# VAM_control_logic_proposal_4_5.net
KiCad netlist of a schematic drawn in EAGLE
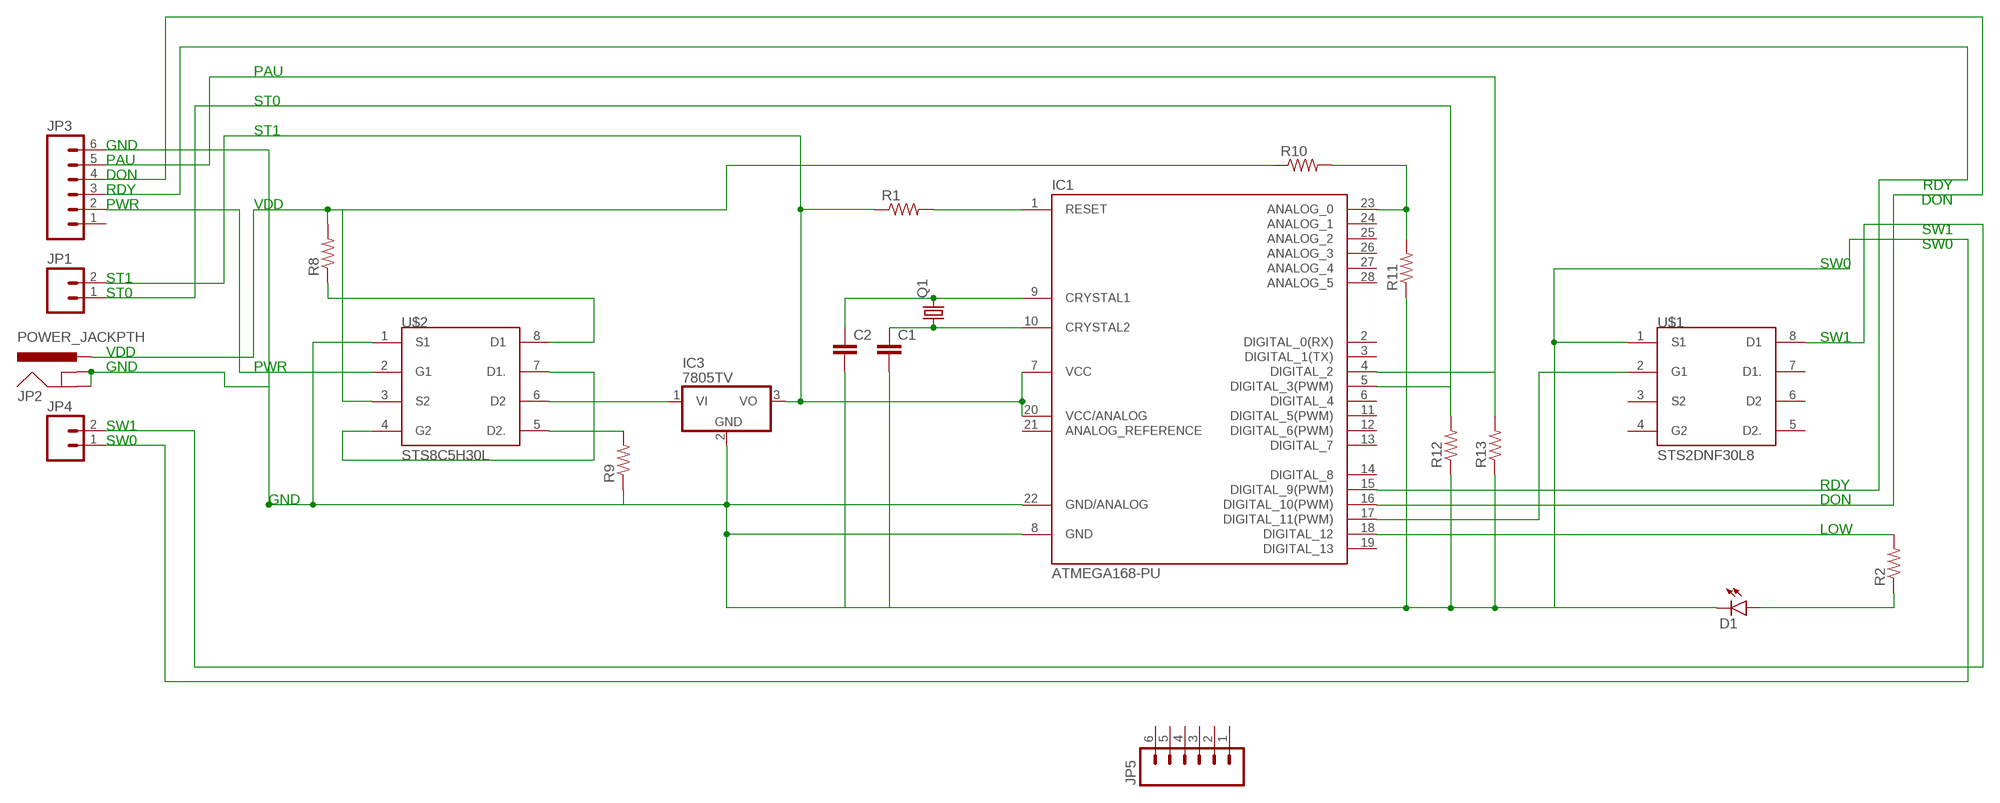
[diagram p0: schematic, sheet 1]

(export (version "E")
  (design (tool "Eeschema 10.0.6"))
  (components
    (comp (ref "C1")
      (value "C-EU025-024X044")
      (footprint "eagle-import:C025-024X044")
      (libsource (lib "eagle-import") (part "C-EU025-024X044"))
    )
    (comp (ref "C2")
      (value "C-EU025-024X044")
      (footprint "eagle-import:C025-024X044")
      (libsource (lib "eagle-import") (part "C-EU025-024X044"))
    )
    (comp (ref "D1")
      (value "LED5MM")
      (footprint "eagle-import:LED5MM")
      (libsource (lib "eagle-import") (part "LED5MM"))
    )
    (comp (ref "IC1")
      (value "ATMEGA168-PU")
      (footprint "eagle-import:DIL28-3")
      (libsource (lib "eagle-import") (part "ATMEGA168-PU"))
    )
    (comp (ref "IC3")
      (value "7805TV")
      (footprint "eagle-import:TO220V")
      (libsource (lib "eagle-import") (part "78TV05"))
    )
    (comp (ref "JP1")
      (value "M02PTH")
      (footprint "eagle-import:1X02")
      (libsource (lib "eagle-import") (part "M02PTH"))
    )
    (comp (ref "JP2")
      (value "POWER_JACKPTH")
      (footprint "eagle-import:POWER_JACK_PTH")
      (libsource (lib "eagle-import") (part "POWER_JACKPTH"))
    )
    (comp (ref "JP3")
      (value "M06SILK_FEMALE_PTH")
      (footprint "eagle-import:1X06")
      (libsource (lib "eagle-import") (part "M06SILK_FEMALE_PTH"))
    )
    (comp (ref "JP4")
      (value "M02PTH")
      (footprint "eagle-import:1X02")
      (libsource (lib "eagle-import") (part "M02PTH"))
    )
    (comp (ref "JP5")
      (value "M06SILK_FEMALE_PTH")
      (footprint "eagle-import:1X06")
      (libsource (lib "eagle-import") (part "M06SILK_FEMALE_PTH"))
    )
    (comp (ref "Q1")
      (value "CRYSTALHC49U-V")
      (footprint "eagle-import:HC49U-V")
      (libsource (lib "eagle-import") (part "CRYSTALHC49U-V"))
    )
    (comp (ref "R1")
      (value "R-US_R1206")
      (footprint "eagle-import:R1206")
      (libsource (lib "eagle-import") (part "R-US_R1206"))
    )
    (comp (ref "R2")
      (value "R-US_R1206")
      (footprint "eagle-import:R1206")
      (libsource (lib "eagle-import") (part "R-US_R1206"))
    )
    (comp (ref "R8")
      (value "R-US_R1206")
      (footprint "eagle-import:R1206")
      (libsource (lib "eagle-import") (part "R-US_R1206"))
    )
    (comp (ref "R9")
      (value "R-US_R1206")
      (footprint "eagle-import:R1206")
      (libsource (lib "eagle-import") (part "R-US_R1206"))
    )
    (comp (ref "R10")
      (value "R-US_R1206")
      (footprint "eagle-import:R1206")
      (libsource (lib "eagle-import") (part "R-US_R1206"))
    )
    (comp (ref "R11")
      (value "R-US_R1206")
      (footprint "eagle-import:R1206")
      (libsource (lib "eagle-import") (part "R-US_R1206"))
    )
    (comp (ref "R12")
      (value "R-US_R1206")
      (footprint "eagle-import:R1206")
      (libsource (lib "eagle-import") (part "R-US_R1206"))
    )
    (comp (ref "R13")
      (value "R-US_R1206")
      (footprint "eagle-import:R1206")
      (libsource (lib "eagle-import") (part "R-US_R1206"))
    )
    (comp (ref "U$1")
      (value "STS2DNF30L8")
      (footprint "eagle-import:SOIC-8")
      (libsource (lib "eagle-import") (part "STS2DNF30L8"))
    )
    (comp (ref "U$2")
      (value "STS8C5H30L")
      (footprint "eagle-import:SOIC-8")
      (libsource (lib "eagle-import") (part "STS2DNF30L8"))
    )
  )
  (nets
    (net (code "1") (name "Net-(D1-C)") (class "Default")
      (node (ref "C1") (pin "2") (pinfunction "2_2") (pintype "passive"))
      (node (ref "C2") (pin "2") (pinfunction "2_2") (pintype "passive"))
      (node (ref "D1") (pin "K") (pinfunction "C_K") (pintype "passive"))
      (node (ref "IC1") (pin "22") (pinfunction "GND/ANALOG_22") (pintype "power_in"))
      (node (ref "IC1") (pin "8") (pinfunction "GND_8") (pintype "power_in"))
      (node (ref "IC3") (pin "2") (pinfunction "GND_2") (pintype "passive"))
      (node (ref "JP2") (pin "GND") (pinfunction "GND_GND") (pintype "bidirectional"))
      (node (ref "JP2") (pin "GNDBREAK") (pinfunction "GNDBREAK_GNDBREAK") (pintype "bidirectional"))
      (node (ref "JP3") (pin "6") (pinfunction "6_6") (pintype "passive"))
      (node (ref "JP4") (pin "1") (pinfunction "1_1") (pintype "passive"))
      (node (ref "R11") (pin "1") (pinfunction "1_1") (pintype "passive"))
      (node (ref "R12") (pin "1") (pinfunction "1_1") (pintype "passive"))
      (node (ref "R13") (pin "1") (pinfunction "1_1") (pintype "passive"))
      (node (ref "R9") (pin "1") (pinfunction "1_1") (pintype "passive"))
      (node (ref "U$1") (pin "1") (pinfunction "S1_1") (pintype "bidirectional"))
      (node (ref "U$2") (pin "1") (pinfunction "S1_1") (pintype "bidirectional"))
    )
    (net (code "2") (name "Net-(D1-PadA)") (class "Default")
      (node (ref "D1") (pin "A") (pinfunction "A_A") (pintype "passive"))
      (node (ref "R2") (pin "1") (pinfunction "1_1") (pintype "passive"))
    )
    (net (code "3") (name "Net-(IC1-ANALOG_0)") (class "Default")
      (node (ref "IC1") (pin "23") (pinfunction "ANALOG_0_23") (pintype "bidirectional"))
      (node (ref "R10") (pin "2") (pinfunction "2_2") (pintype "passive"))
      (node (ref "R11") (pin "2") (pinfunction "2_2") (pintype "passive"))
    )
    (net (code "4") (name "Net-(IC1-CRYSTAL1)") (class "Default")
      (node (ref "C2") (pin "1") (pinfunction "1_1") (pintype "passive"))
      (node (ref "IC1") (pin "9") (pinfunction "CRYSTAL1_9") (pintype "bidirectional"))
      (node (ref "Q1") (pin "2") (pinfunction "2_2") (pintype "passive"))
    )
    (net (code "5") (name "Net-(IC1-CRYSTAL2)") (class "Default")
      (node (ref "C1") (pin "1") (pinfunction "1_1") (pintype "passive"))
      (node (ref "IC1") (pin "10") (pinfunction "CRYSTAL2_10") (pintype "bidirectional"))
      (node (ref "Q1") (pin "1") (pinfunction "1_1") (pintype "passive"))
    )
    (net (code "6") (name "Net-(IC1-DIGITAL_2)") (class "Default")
      (node (ref "IC1") (pin "4") (pinfunction "DIGITAL_2_4") (pintype "bidirectional"))
      (node (ref "JP3") (pin "5") (pinfunction "5_5") (pintype "passive"))
      (node (ref "R13") (pin "2") (pinfunction "2_2") (pintype "passive"))
    )
    (net (code "7") (name "Net-(IC1-DIGITAL_3(PWM))") (class "Default")
      (node (ref "IC1") (pin "5") (pinfunction "DIGITAL_3(PWM)_5") (pintype "bidirectional"))
      (node (ref "JP1") (pin "1") (pinfunction "1_1") (pintype "passive"))
      (node (ref "R12") (pin "2") (pinfunction "2_2") (pintype "passive"))
    )
    (net (code "8") (name "Net-(IC1-DIGITAL_9(PWM))") (class "Default")
      (node (ref "IC1") (pin "15") (pinfunction "DIGITAL_9(PWM)_15") (pintype "bidirectional"))
      (node (ref "JP3") (pin "3") (pinfunction "3_3") (pintype "passive"))
    )
    (net (code "9") (name "Net-(IC1-DIGITAL_10(PWM))") (class "Default")
      (node (ref "IC1") (pin "16") (pinfunction "DIGITAL_10(PWM)_16") (pintype "bidirectional"))
      (node (ref "JP3") (pin "4") (pinfunction "4_4") (pintype "passive"))
    )
    (net (code "10") (name "Net-(IC1-DIGITAL_11(PWM))") (class "Default")
      (node (ref "IC1") (pin "17") (pinfunction "DIGITAL_11(PWM)_17") (pintype "bidirectional"))
      (node (ref "U$1") (pin "2") (pinfunction "G1_2") (pintype "bidirectional"))
    )
    (net (code "11") (name "Net-(IC1-DIGITAL_12)") (class "Default")
      (node (ref "IC1") (pin "18") (pinfunction "DIGITAL_12_18") (pintype "bidirectional"))
      (node (ref "R2") (pin "2") (pinfunction "2_2") (pintype "passive"))
    )
    (net (code "12") (name "Net-(IC1-RESET)") (class "Default")
      (node (ref "IC1") (pin "1") (pinfunction "RESET_1") (pintype "bidirectional"))
      (node (ref "R1") (pin "2") (pinfunction "2_2") (pintype "passive"))
    )
    (net (code "13") (name "Net-(IC1-VCC)") (class "Default")
      (node (ref "IC1") (pin "20") (pinfunction "VCC/ANALOG_20") (pintype "passive"))
      (node (ref "IC1") (pin "7") (pinfunction "VCC_7") (pintype "power_in"))
      (node (ref "IC3") (pin "3") (pinfunction "VO_3") (pintype "passive"))
      (node (ref "JP1") (pin "2") (pinfunction "2_2") (pintype "passive"))
      (node (ref "R1") (pin "1") (pinfunction "1_1") (pintype "passive"))
    )
    (net (code "14") (name "Net-(IC3-VI)") (class "Default")
      (node (ref "IC3") (pin "1") (pinfunction "VI_1") (pintype "input"))
      (node (ref "U$2") (pin "6") (pinfunction "D2_6") (pintype "bidirectional"))
    )
    (net (code "15") (name "Net-(U$1-D1)") (class "Default")
      (node (ref "JP4") (pin "2") (pinfunction "2_2") (pintype "passive"))
      (node (ref "U$1") (pin "8") (pinfunction "D1_8") (pintype "bidirectional"))
    )
    (net (code "16") (name "Net-(U$2-D1)") (class "Default")
      (node (ref "R8") (pin "1") (pinfunction "1_1") (pintype "passive"))
      (node (ref "U$2") (pin "8") (pinfunction "D1_8") (pintype "bidirectional"))
    )
    (net (code "17") (name "Net-(U$2-D1.)") (class "Default")
      (node (ref "U$2") (pin "4") (pinfunction "G2_4") (pintype "bidirectional"))
      (node (ref "U$2") (pin "7") (pinfunction "D1._7") (pintype "bidirectional"))
    )
    (net (code "18") (name "Net-(U$2-D2.)") (class "Default")
      (node (ref "R9") (pin "2") (pinfunction "2_2") (pintype "passive"))
      (node (ref "U$2") (pin "5") (pinfunction "D2._5") (pintype "bidirectional"))
    )
    (net (code "19") (name "Net-(U$2-G1)") (class "Default")
      (node (ref "JP3") (pin "2") (pinfunction "2_2") (pintype "passive"))
      (node (ref "U$2") (pin "2") (pinfunction "G1_2") (pintype "bidirectional"))
    )
    (net (code "20") (name "Net-(U$2-S2)") (class "Default")
      (node (ref "JP2") (pin "PWR") (pinfunction "PWR_PWR") (pintype "bidirectional"))
      (node (ref "R10") (pin "1") (pinfunction "1_1") (pintype "passive"))
      (node (ref "R8") (pin "2") (pinfunction "2_2") (pintype "passive"))
      (node (ref "U$2") (pin "3") (pinfunction "S2_3") (pintype "bidirectional"))
    )
    (net (code "21") (name "unconnected-(IC1-ANALOG_1-Pad24)") (class "Default")
      (node (ref "IC1") (pin "24") (pinfunction "ANALOG_1_24") (pintype "bidirectional"))
    )
    (net (code "22") (name "unconnected-(IC1-ANALOG_2-Pad25)") (class "Default")
      (node (ref "IC1") (pin "25") (pinfunction "ANALOG_2_25") (pintype "bidirectional"))
    )
    (net (code "23") (name "unconnected-(IC1-ANALOG_3-Pad26)") (class "Default")
      (node (ref "IC1") (pin "26") (pinfunction "ANALOG_3_26") (pintype "bidirectional"))
    )
    (net (code "24") (name "unconnected-(IC1-ANALOG_4-Pad27)") (class "Default")
      (node (ref "IC1") (pin "27") (pinfunction "ANALOG_4_27") (pintype "bidirectional"))
    )
    (net (code "25") (name "unconnected-(IC1-ANALOG_5-Pad28)") (class "Default")
      (node (ref "IC1") (pin "28") (pinfunction "ANALOG_5_28") (pintype "bidirectional"))
    )
    (net (code "26") (name "unconnected-(IC1-ANALOG_REFERENCE-Pad21)") (class "Default")
      (node (ref "IC1") (pin "21") (pinfunction "ANALOG_REFERENCE_21") (pintype "passive"))
    )
    (net (code "27") (name "unconnected-(IC1-DIGITAL_0(RX)-Pad2)") (class "Default")
      (node (ref "IC1") (pin "2") (pinfunction "DIGITAL_0(RX)_2") (pintype "bidirectional"))
    )
    (net (code "28") (name "unconnected-(IC1-DIGITAL_1(TX)-Pad3)") (class "Default")
      (node (ref "IC1") (pin "3") (pinfunction "DIGITAL_1(TX)_3") (pintype "bidirectional"))
    )
    (net (code "29") (name "unconnected-(IC1-DIGITAL_4-Pad6)") (class "Default")
      (node (ref "IC1") (pin "6") (pinfunction "DIGITAL_4_6") (pintype "bidirectional"))
    )
    (net (code "30") (name "unconnected-(IC1-DIGITAL_5(PWM)-Pad11)") (class "Default")
      (node (ref "IC1") (pin "11") (pinfunction "DIGITAL_5(PWM)_11") (pintype "bidirectional"))
    )
    (net (code "31") (name "unconnected-(IC1-DIGITAL_6(PWM)-Pad12)") (class "Default")
      (node (ref "IC1") (pin "12") (pinfunction "DIGITAL_6(PWM)_12") (pintype "bidirectional"))
    )
    (net (code "32") (name "unconnected-(IC1-DIGITAL_7-Pad13)") (class "Default")
      (node (ref "IC1") (pin "13") (pinfunction "DIGITAL_7_13") (pintype "bidirectional"))
    )
    (net (code "33") (name "unconnected-(IC1-DIGITAL_8-Pad14)") (class "Default")
      (node (ref "IC1") (pin "14") (pinfunction "DIGITAL_8_14") (pintype "bidirectional"))
    )
    (net (code "34") (name "unconnected-(IC1-DIGITAL_13-Pad19)") (class "Default")
      (node (ref "IC1") (pin "19") (pinfunction "DIGITAL_13_19") (pintype "bidirectional"))
    )
    (net (code "35") (name "unconnected-(JP3-Pad1)") (class "Default")
      (node (ref "JP3") (pin "1") (pinfunction "1_1") (pintype "passive"))
    )
    (net (code "36") (name "unconnected-(JP5-Pad1)") (class "Default")
      (node (ref "JP5") (pin "1") (pinfunction "1_1") (pintype "passive"))
    )
    (net (code "37") (name "unconnected-(JP5-Pad2)") (class "Default")
      (node (ref "JP5") (pin "2") (pinfunction "2_2") (pintype "passive"))
    )
    (net (code "38") (name "unconnected-(JP5-Pad3)") (class "Default")
      (node (ref "JP5") (pin "3") (pinfunction "3_3") (pintype "passive"))
    )
    (net (code "39") (name "unconnected-(JP5-Pad4)") (class "Default")
      (node (ref "JP5") (pin "4") (pinfunction "4_4") (pintype "passive"))
    )
    (net (code "40") (name "unconnected-(JP5-Pad5)") (class "Default")
      (node (ref "JP5") (pin "5") (pinfunction "5_5") (pintype "passive"))
    )
    (net (code "41") (name "unconnected-(JP5-Pad6)") (class "Default")
      (node (ref "JP5") (pin "6") (pinfunction "6_6") (pintype "passive"))
    )
    (net (code "42") (name "unconnected-(U$1-D1.-Pad7)") (class "Default")
      (node (ref "U$1") (pin "7") (pinfunction "D1._7") (pintype "bidirectional"))
    )
    (net (code "43") (name "unconnected-(U$1-D2-Pad6)") (class "Default")
      (node (ref "U$1") (pin "6") (pinfunction "D2_6") (pintype "bidirectional"))
    )
    (net (code "44") (name "unconnected-(U$1-D2.-Pad5)") (class "Default")
      (node (ref "U$1") (pin "5") (pinfunction "D2._5") (pintype "bidirectional"))
    )
    (net (code "45") (name "unconnected-(U$1-G2-Pad4)") (class "Default")
      (node (ref "U$1") (pin "4") (pinfunction "G2_4") (pintype "bidirectional"))
    )
    (net (code "46") (name "unconnected-(U$1-S2-Pad3)") (class "Default")
      (node (ref "U$1") (pin "3") (pinfunction "S2_3") (pintype "bidirectional"))
    )
  )
)
